# P00160_5_868_P.net
KiCad netlist of a schematic drawn in Altium Designer
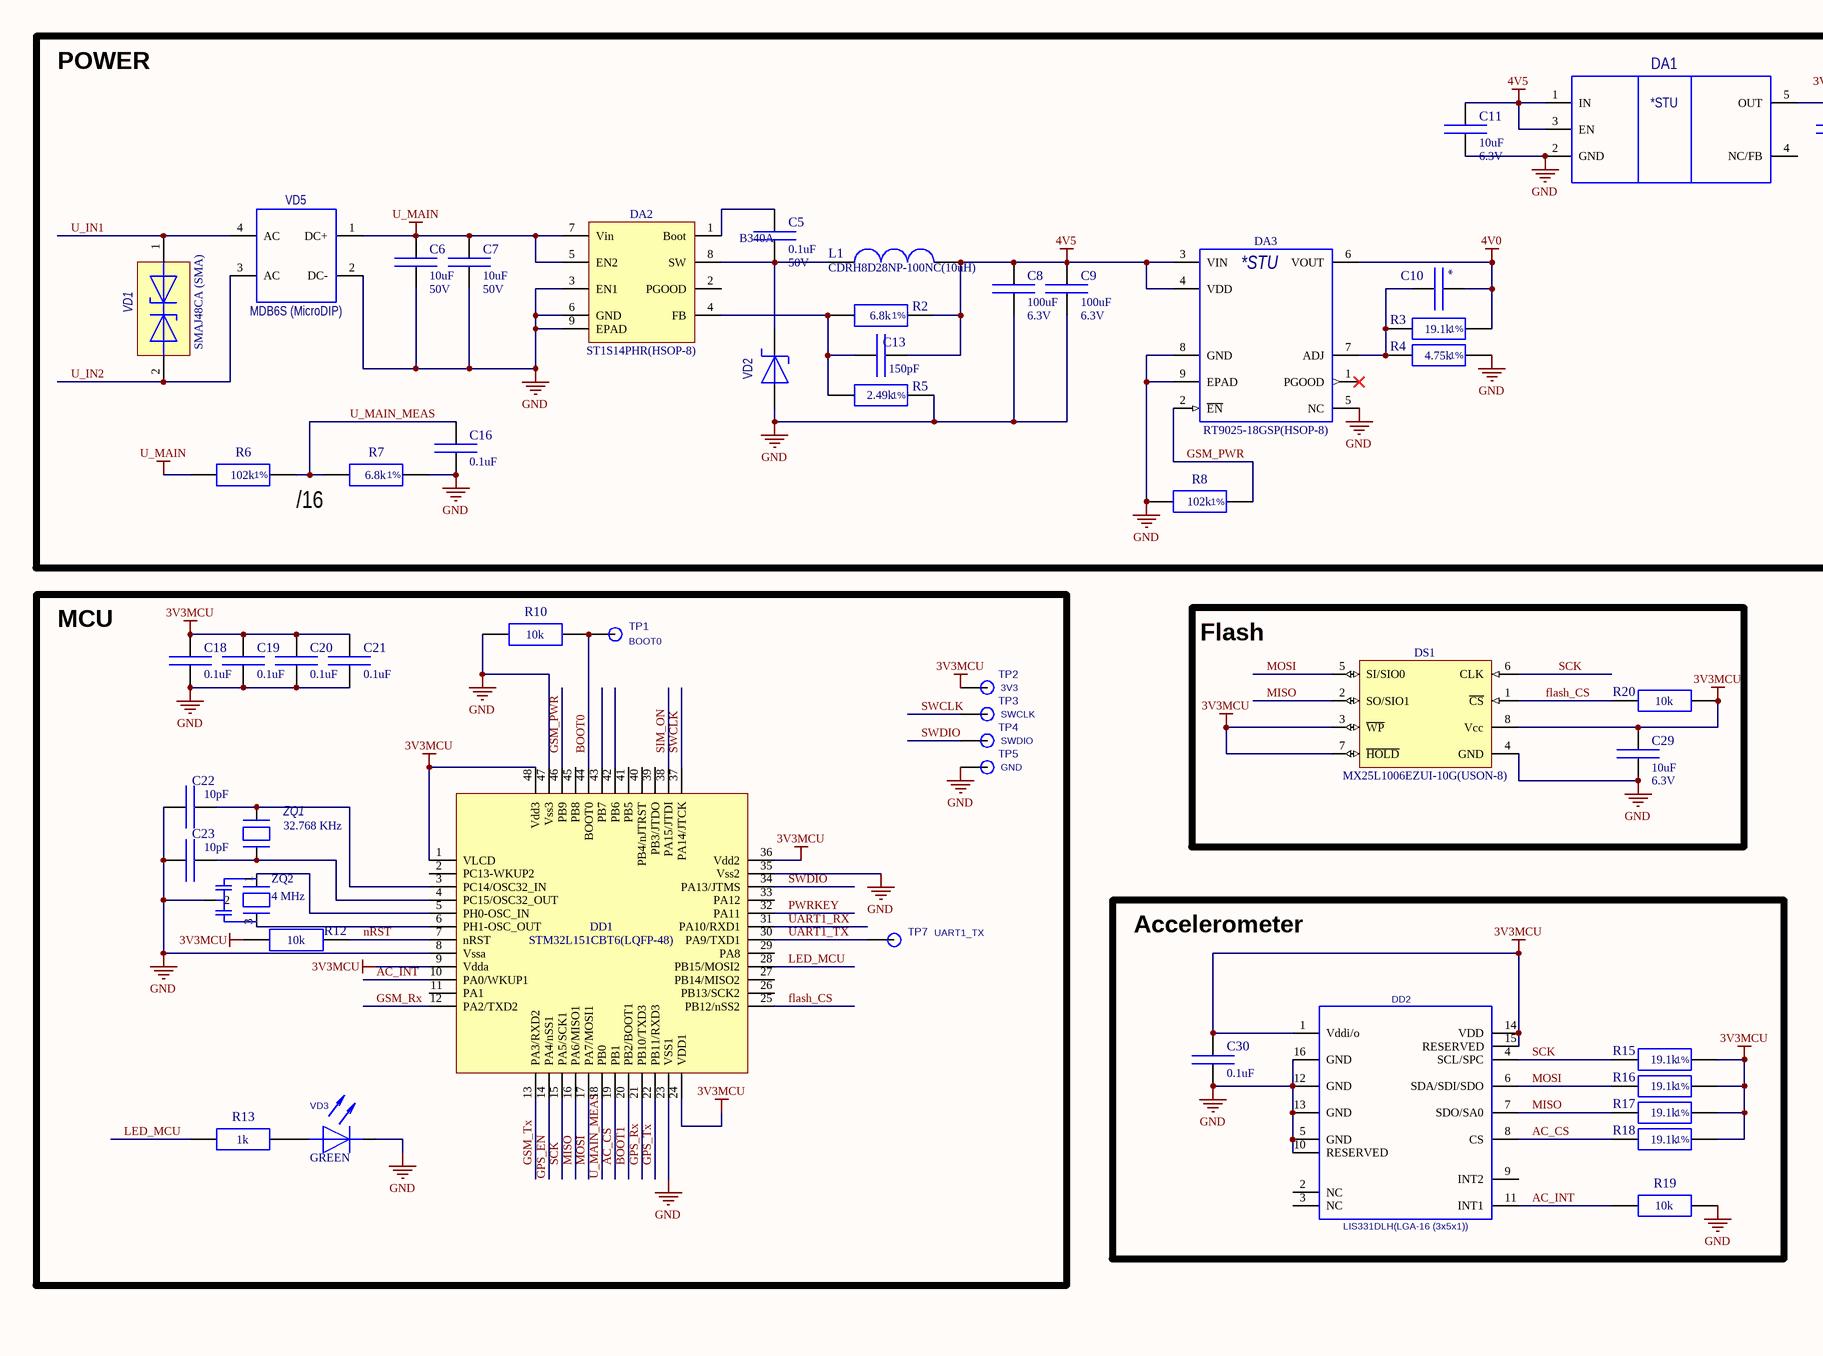
[diagram p0: P00160.5_868_P.SchDoc, left]
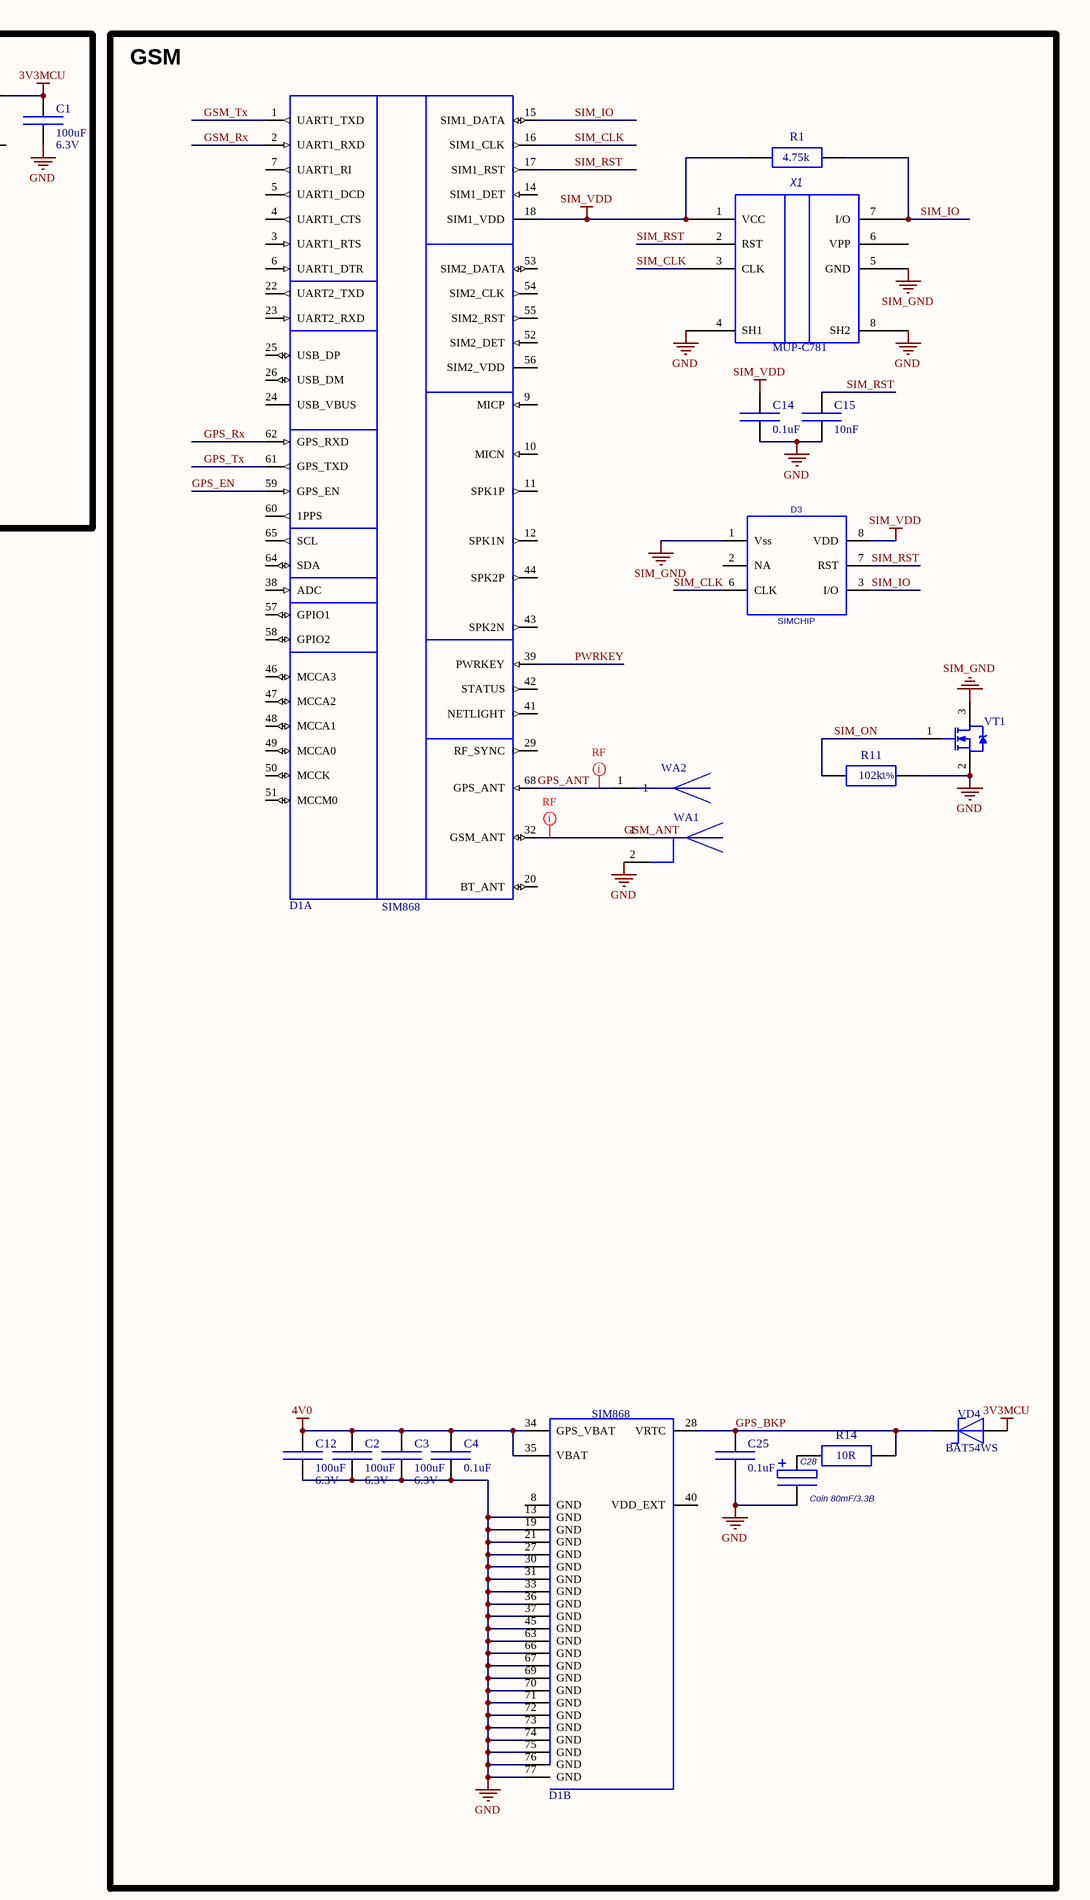
[diagram p1: P00160.5_868_P.SchDoc, right]

(export (version "E")
  (design (tool "Eeschema 10.0.6"))
  (components
    (comp (ref "C1")
      (value "100uF")
      (footprint "CAPC3216X135(1206)")
      (description "C1206")
      (fields (field (name "PARVOLTAGE") "6.3V") (field (name "Comment") "чип 1206 100uF/6.3V, "))
      (libsource (lib "pass_smd") (part "C1206"))
    )
    (comp (ref "C2")
      (value "100uF")
      (footprint "CAPC3216X135(1206)")
      (description "C1206")
      (fields (field (name "PARVOLTAGE") "6.3V") (field (name "Comment") "чип 1206 100uF/6.3V, "))
      (libsource (lib "pass_smd") (part "C1206"))
    )
    (comp (ref "C3")
      (value "100uF")
      (footprint "CAPC3216X135(1206)")
      (description "C1206")
      (fields (field (name "PARVOLTAGE") "6.3V") (field (name "Comment") "чип 1206 100uF/6.3V, "))
      (libsource (lib "pass_smd") (part "C1206"))
    )
    (comp (ref "C4")
      (value "0.1uF")
      (footprint "CAPC1005X50(0402)")
      (description "C0402")
      (fields (field (name "Comment") "чип 0402 0.1uF/10V, "))
      (libsource (lib "pass_smd") (part "C0402"))
    )
    (comp (ref "C5")
      (value "0.1uF")
      (footprint "CAPC1608X50(0603)")
      (description "C0603")
      (fields (field (name "PARVOLTAGE") "50V") (field (name "Comment") "чип 0603 0.1uF/50V, "))
      (libsource (lib "pass_smd") (part "C0603"))
    )
    (comp (ref "C6")
      (value "10uF")
      (footprint "CAPC3216X135(1206)")
      (description "C1206")
      (fields
        (field (name "CMPPARTNUM") "CL31A106KBHNNNE")
        (field (name "PARVOLTAGE") "50V")
        (field (name "Comment") "чип 1206 10uF/50V, ")
      )
      (libsource (lib "pass_smd") (part "C1206"))
    )
    (comp (ref "C7")
      (value "10uF")
      (footprint "CAPC3216X135(1206)")
      (description "C1206")
      (fields
        (field (name "CMPPARTNUM") "CL31A106KBHNNNE")
        (field (name "PARVOLTAGE") "50V")
        (field (name "Comment") "чип 1206 10uF/50V, ")
      )
      (libsource (lib "pass_smd") (part "C1206"))
    )
    (comp (ref "C8")
      (value "100uF")
      (footprint "CAPC3216X135(1206)")
      (description "C1206")
      (fields (field (name "PARVOLTAGE") "6.3V") (field (name "Comment") "чип 1206 100uF/6.3V, "))
      (libsource (lib "pass_smd") (part "C1206"))
    )
    (comp (ref "C9")
      (value "100uF")
      (footprint "CAPC3216X135(1206)")
      (description "C1206")
      (fields (field (name "PARVOLTAGE") "6.3V") (field (name "Comment") "чип 1206 100uF/6.3V, "))
      (libsource (lib "pass_smd") (part "C1206"))
    )
    (comp (ref "C10")
      (value "чип 0402 */,")
      (footprint "CAPC1005X50(0402)")
      (description "C0402")
      (fields (field (name "ALTIUM_VALUE") "*"))
      (libsource (lib "pass_smd") (part "C0402"))
    )
    (comp (ref "C11")
      (value "10uF")
      (footprint "CAPC1608X50(0603)")
      (description "C0603")
      (fields (field (name "PARVOLTAGE") "6.3V") (field (name "Comment") "чип 0603 10uF/6.3V, "))
      (libsource (lib "pass_smd") (part "C0603"))
    )
    (comp (ref "C12")
      (value "100uF")
      (footprint "CAPC3216X135(1206)")
      (description "C1206")
      (fields (field (name "PARVOLTAGE") "6.3V") (field (name "Comment") "чип 1206 100uF/6.3V, "))
      (libsource (lib "pass_smd") (part "C1206"))
    )
    (comp (ref "C13")
      (value "150pF")
      (footprint "CAPC1005X50(0402)")
      (description "C0402")
      (fields (field (name "Comment") "чип 0402 150pF/50V, "))
      (libsource (lib "pass_smd") (part "C0402"))
    )
    (comp (ref "C14")
      (value "0.1uF")
      (footprint "CAPC1005X50(0402)")
      (description "C0402")
      (fields (field (name "Comment") "чип 0402 0.1uF/10V, "))
      (libsource (lib "pass_smd") (part "C0402"))
    )
    (comp (ref "C15")
      (value "10nF")
      (footprint "CAPC1005X50(0402)")
      (description "C0402")
      (fields (field (name "Comment") "чип 0402 10nF/10V, "))
      (libsource (lib "pass_smd") (part "C0402"))
    )
    (comp (ref "C16")
      (value "0.1uF")
      (footprint "CAPC1005X50(0402)")
      (description "C0402")
      (fields (field (name "Comment") "чип 0402 0.1uF/10V, "))
      (libsource (lib "pass_smd") (part "C0402"))
    )
    (comp (ref "C18")
      (value "0.1uF")
      (footprint "CAPC1005X50(0402)")
      (description "C0402")
      (fields (field (name "Comment") "чип 0402 0.1uF/10V, "))
      (libsource (lib "pass_smd") (part "C0402"))
    )
    (comp (ref "C19")
      (value "0.1uF")
      (footprint "CAPC1005X50(0402)")
      (description "C0402")
      (fields (field (name "Comment") "чип 0402 0.1uF/10V, "))
      (libsource (lib "pass_smd") (part "C0402"))
    )
    (comp (ref "C20")
      (value "0.1uF")
      (footprint "CAPC1005X50(0402)")
      (description "C0402")
      (fields (field (name "Comment") "чип 0402 0.1uF/10V, "))
      (libsource (lib "pass_smd") (part "C0402"))
    )
    (comp (ref "C21")
      (value "0.1uF")
      (footprint "CAPC1005X50(0402)")
      (description "C0402")
      (fields (field (name "Comment") "чип 0402 0.1uF/10V, "))
      (libsource (lib "pass_smd") (part "C0402"))
    )
    (comp (ref "C22")
      (value "10pF")
      (footprint "CAPC1005X50(0402)")
      (description "C0402")
      (fields (field (name "Comment") "чип 0402 10pF/10V, "))
      (libsource (lib "pass_smd") (part "C0402"))
    )
    (comp (ref "C23")
      (value "10pF")
      (footprint "CAPC1005X50(0402)")
      (description "C0402")
      (fields (field (name "Comment") "чип 0402 10pF/10V, "))
      (libsource (lib "pass_smd") (part "C0402"))
    )
    (comp (ref "C25")
      (value "0.1uF")
      (footprint "CAPC1005X50(0402)")
      (description "C0402")
      (fields (field (name "Comment") "чип 0402 0.1uF/10V, "))
      (libsource (lib "pass_smd") (part "C0402"))
    )
    (comp (ref "C28")
      (value "Coin 80mF/3.3В")
      (footprint "XH414HG-IV01E")
      (description "ELECTRIC DOUBLE LAYER CAPACITORS")
      (fields (field (name "CMPPARTNUM") "XH414HG-IV01E"))
      (libsource (lib "MyLib") (part "XH414HG-IV01E"))
    )
    (comp (ref "C29")
      (value "10uF")
      (footprint "CAPC1608X50(0603)")
      (description "C0603")
      (fields (field (name "PARVOLTAGE") "6.3V") (field (name "Comment") "чип 0603 10uF/6.3V, "))
      (libsource (lib "pass_smd") (part "C0603"))
    )
    (comp (ref "C30")
      (value "0.1uF")
      (footprint "CAPC1005X50(0402)")
      (description "C0402")
      (fields (field (name "Comment") "чип 0402 0.1uF/10V, "))
      (libsource (lib "pass_smd") (part "C0402"))
    )
    (comp (ref "D1") (value "SIM868") (footprint "SIM868") (libsource (lib "") (part "SIM868_1")))
    (comp (ref "D3")
      (value "SIMCHIP")
      (footprint "VQFN127P600-8N")
      (fields (field (name "CMPPARTNUM") "MFF2 SIM"))
      (libsource (lib "Misc") (part "SIMCHIP"))
    )
    (comp (ref "DA1")
      (value "TPS76333DBV(SOT23-5)")
      (footprint "SOT95P285X130-5N(SOT23-5)")
      (description "TPS76333DBV")
      (libsource (lib "TI") (part "TPS76333DBV"))
    )
    (comp (ref "DA2")
      (value "ST1S14PHR(HSOP-8)")
      (footprint "HSOP127P-8N")
      (fields (field (name "CMPPARTNUM") "ST1S14PHR"))
      (libsource (lib "ST") (part "ST1S14"))
    )
    (comp (ref "DA3")
      (value "RT9025-18GSP(HSOP-8)")
      (footprint "HSOP127P-8N")
      (description "2A, Ultra Low Dropout LDO")
      (fields (field (name "CMPPARTNUM") "RT9025-18GSP"))
      (libsource (lib "Richtek") (part "RT9025"))
    )
    (comp (ref "DD1")
      (value "STM32L151CBT6(LQFP-48)")
      (footprint "TSQFP50P900X900X160-48N")
      (description "STM32L151CxU6")
      (fields (field (name "CMPPARTNUM") "STM32L151CBT6"))
      (libsource (lib "ST") (part "STM32L151CxU6"))
    )
    (comp (ref "DD2")
      (value "LIS331DLH(LGA-16 (3x5x1))")
      (footprint "LGA16S50P3X5_300X300X100")
      (description "MEMS digital output motion sensor  ultra low-power high performance 3-axes “nano” accelerometer")
      (fields (field (name "CMPPARTNUM") "LIS331DLH"))
      (libsource (lib "ST") (part "LIS331DLH"))
    )
    (comp (ref "DS1")
      (value "MX25L1006EZUI-10G(USON-8)")
      (footprint "SON50P300X60_HS-9N")
      (description "1M-BIT [x 1/x 2] CMOS SERIAL FLASH")
      (fields (field (name "CMPPARTNUM") "MX25L1006EZUI-10G"))
      (libsource (lib "ROMs") (part "MX25L1006E"))
    )
    (comp (ref "L1")
      (value "CDRH8D28NP-100NC(10uH)")
      (footprint "CDRH8D28NP")
      (description "CDRH8D28NP")
      (fields (field (name "CMPPARTNUM") "CDRH8D28NP-100NC"))
      (libsource (lib "pass_smd") (part "CDRH8D28NP"))
    )
    (comp (ref "R1")
      (value "4.75k")
      (footprint "RESC1005X35(0402)")
      (description "R0402")
      (fields (field (name "TOLERANCE") "1%") (field (name "Comment") "чип 0402 4.75k 1%"))
      (libsource (lib "pass_smd") (part "R0402"))
    )
    (comp (ref "R2")
      (value "6.8k")
      (footprint "RESC1005X35(0402)")
      (description "R0402")
      (fields (field (name "TOLERANCE") "1%") (field (name "Comment") "чип 0402 6.8k 1%"))
      (libsource (lib "pass_smd") (part "R0402"))
    )
    (comp (ref "R3")
      (value "19.1k")
      (footprint "RESC1005X35(0402)")
      (description "R0402")
      (fields (field (name "TOLERANCE") "1%") (field (name "Comment") "чип 0402 19.1k 1%"))
      (libsource (lib "pass_smd") (part "R0402"))
    )
    (comp (ref "R4")
      (value "4.75k")
      (footprint "RESC1005X35(0402)")
      (description "R0402")
      (fields (field (name "TOLERANCE") "1%") (field (name "Comment") "чип 0402 4.75k 1%"))
      (libsource (lib "pass_smd") (part "R0402"))
    )
    (comp (ref "R5")
      (value "2.49k")
      (footprint "RESC1005X35(0402)")
      (description "R0402")
      (fields (field (name "TOLERANCE") "1%") (field (name "Comment") "чип 0402 2.49k 1%"))
      (libsource (lib "pass_smd") (part "R0402"))
    )
    (comp (ref "R6")
      (value "102k")
      (footprint "RESC1005X35(0402)")
      (description "R0402")
      (fields (field (name "TOLERANCE") "1%") (field (name "Comment") "чип 0402 102k 1%"))
      (libsource (lib "pass_smd") (part "R0402"))
    )
    (comp (ref "R7")
      (value "6.8k")
      (footprint "RESC1005X35(0402)")
      (description "R0402")
      (fields (field (name "TOLERANCE") "1%") (field (name "Comment") "чип 0402 6.8k 1%"))
      (libsource (lib "pass_smd") (part "R0402"))
    )
    (comp (ref "R8")
      (value "102k")
      (footprint "RESC1005X35(0402)")
      (description "R0402")
      (fields (field (name "TOLERANCE") "1%") (field (name "Comment") "чип 0402 102k 1%"))
      (libsource (lib "pass_smd") (part "R0402"))
    )
    (comp (ref "R10")
      (value "10k")
      (footprint "RESC1005X35(0402)")
      (description "R0402")
      (fields (field (name "TOLERANCE") "5%") (field (name "Comment") "чип 0402 10k 5%"))
      (libsource (lib "pass_smd") (part "R0402"))
    )
    (comp (ref "R11")
      (value "102k")
      (footprint "RESC1005X35(0402)")
      (description "R0402")
      (fields (field (name "TOLERANCE") "1%") (field (name "Comment") "чип 0402 102k 1%"))
      (libsource (lib "pass_smd") (part "R0402"))
    )
    (comp (ref "R12")
      (value "10k")
      (footprint "RESC1005X35(0402)")
      (description "R0402")
      (fields (field (name "TOLERANCE") "5%") (field (name "Comment") "чип 0402 10k 5%"))
      (libsource (lib "pass_smd") (part "R0402"))
    )
    (comp (ref "R13")
      (value "1k")
      (footprint "RESC1005X35(0402)")
      (description "R0402")
      (fields (field (name "TOLERANCE") "5%") (field (name "Comment") "чип 0402 1k 5%"))
      (libsource (lib "pass_smd") (part "R0402"))
    )
    (comp (ref "R14")
      (value "10R")
      (footprint "RESC1005X35(0402)")
      (description "R0402")
      (fields (field (name "TOLERANCE") "5%") (field (name "Comment") "чип 0402 10R 5%"))
      (libsource (lib "pass_smd") (part "R0402"))
    )
    (comp (ref "R15")
      (value "19.1k")
      (footprint "RESC1005X35(0402)")
      (description "R0402")
      (fields (field (name "TOLERANCE") "1%") (field (name "Comment") "чип 0402 19.1k 1%"))
      (libsource (lib "pass_smd") (part "R0402"))
    )
    (comp (ref "R16")
      (value "19.1k")
      (footprint "RESC1005X35(0402)")
      (description "R0402")
      (fields (field (name "TOLERANCE") "1%") (field (name "Comment") "чип 0402 19.1k 1%"))
      (libsource (lib "pass_smd") (part "R0402"))
    )
    (comp (ref "R17")
      (value "19.1k")
      (footprint "RESC1005X35(0402)")
      (description "R0402")
      (fields (field (name "TOLERANCE") "1%") (field (name "Comment") "чип 0402 19.1k 1%"))
      (libsource (lib "pass_smd") (part "R0402"))
    )
    (comp (ref "R18")
      (value "19.1k")
      (footprint "RESC1005X35(0402)")
      (description "R0402")
      (fields (field (name "TOLERANCE") "1%") (field (name "Comment") "чип 0402 19.1k 1%"))
      (libsource (lib "pass_smd") (part "R0402"))
    )
    (comp (ref "R19")
      (value "10k")
      (footprint "RESC1005X35(0402)")
      (description "R0402")
      (fields (field (name "TOLERANCE") "5%") (field (name "Comment") "чип 0402 10k 5%"))
      (libsource (lib "pass_smd") (part "R0402"))
    )
    (comp (ref "R20")
      (value "10k")
      (footprint "RESC1005X35(0402)")
      (description "R0402")
      (fields (field (name "TOLERANCE") "5%") (field (name "Comment") "чип 0402 10k 5%"))
      (libsource (lib "pass_smd") (part "R0402"))
    )
    (comp (ref "TP1")
      (value "BOOT0")
      (footprint "TEST_POINT")
      (description "TEST_POINT")
      (libsource (lib "connectors") (part "TEST_POINT"))
    )
    (comp (ref "TP2")
      (value "3V3")
      (footprint "TEST_POINT")
      (description "TEST_POINT")
      (libsource (lib "connectors") (part "TEST_POINT"))
    )
    (comp (ref "TP3")
      (value "SWCLK")
      (footprint "TEST_POINT")
      (description "TEST_POINT")
      (libsource (lib "connectors") (part "TEST_POINT"))
    )
    (comp (ref "TP4")
      (value "SWDIO")
      (footprint "TEST_POINT")
      (description "TEST_POINT")
      (libsource (lib "connectors") (part "TEST_POINT"))
    )
    (comp (ref "TP5")
      (value "GND")
      (footprint "TEST_POINT")
      (description "TEST_POINT")
      (libsource (lib "connectors") (part "TEST_POINT"))
    )
    (comp (ref "TP7")
      (value "UART1_TX")
      (footprint "TEST_POINT")
      (description "TEST_POINT")
      (libsource (lib "connectors") (part "TEST_POINT"))
    )
    (comp (ref "VD1")
      (value "SMAJ48CA (SMA)")
      (footprint "DIOM5226X267N (SMA) B")
      (description "Zener (TVS) Diode in SMA package Bidirectional")
      (fields (field (name "CMPPARTNUM") "SMAJ48CA"))
      (libsource (lib "diodes") (part "SMA Zener (Bidir)"))
    )
    (comp (ref "VD2")
      (value "B340A (SMA)")
      (footprint "DIOM5226X267N (SMA)")
      (description "Schottky diode in SMA Case")
      (fields (field (name "CMPPARTNUM") "B340A"))
      (libsource (lib "diodes") (part "SMA SCHOTTKY"))
    )
    (comp (ref "VD3")
      (value "APHHS1005SURCK (чип 0402)")
      (footprint "LED1005X50N(0402)_GREEN")
      (description "LED 0402")
      (fields (field (name "CMPPARTNUM") "APHHS1005SURCK") (field (name "PARCOLOR") "GREEN"))
      (libsource (lib "diodes") (part "LED 0402"))
    )
    (comp (ref "VD4")
      (value "BAT54WS (SOD323)")
      (footprint "SOD2514X110N(SOD323)")
      (description "BAT54WS")
      (fields (field (name "CMPPARTNUM") "BAT54WS"))
      (libsource (lib "diodes") (part "SOD323 SCHOTTKY"))
    )
    (comp (ref "VD5")
      (value "MDB6S (MicroDIP)")
      (footprint "Micro-DIP")
      (description "B1S-B10S 0.5 surface mount glass passivated bridge rectifier")
      (fields (field (name "CMPPARTNUM") "MDB6S"))
      (libsource (lib "diodes") (part "MDB6S"))
    )
    (comp (ref "VT1")
      (value "IRLML0030TRPBF (SOT-23)")
      (footprint "SOT95P230-3N (SOT-23) num")
      (description "HEXFET Power MOSFET")
      (fields (field (name "CMPPARTNUM") "IRLML0030TRPBF"))
      (libsource (lib "transistors") (part "IRLML0030"))
    )
    (comp (ref "WA1")
      (value "~")
      (footprint "PCB_ANT")
      (description "CLIP_ANT")
      (libsource (lib "MyLib") (part "ANT_PCB_CLIP"))
    )
    (comp (ref "WA2")
      (value "UDA182-180-1575-C-GPS-GLONASS-PCB")
      (footprint "UDA184")
      (description "A25, UDA25, A18")
      (libsource (lib "Misc") (part "GPS antenna Pass"))
    )
    (comp (ref "X1")
      (value "MUP Connectors MUP-C781")
      (footprint "MUP-C781")
      (description "Sim Holder MUP-C781")
      (fields (field (name "CMPPARTNUM") "MUP-C781"))
      (libsource (lib "connectors") (part "SIM MUP-C781"))
    )
    (comp (ref "ZQ1")
      (value "32.768 KHz")
      (footprint "XTAL320X150X90-2N(DST)")
      (description "DST310S")
      (fields (field (name "Comment") "DST310S(32.768 KHz)"))
      (libsource (lib "xtal") (part "XTAL, SMD, 3.2mm x 1.5mm, 2 pads"))
    )
    (comp (ref "ZQ2")
      (value "4 MHz")
      (footprint "XTAL450X200X120 (CSTCR)")
      (description "CSTCR_G15C Ceramic Resonators")
      (fields (field (name "CMPPARTNUM") "CSTCR4M00G15C99-R0") (field (name "TOLERANCE") "±0.5%"))
      (libsource (lib "xtal") (part "XTAL, SMD, 4.5mm x 2mm, 3 pads"))
    )
  )
  (nets
    (net (code "1") (name "/AC_CS") (class "Default")
      (node (ref "DD1") (pin "19") (pinfunction "PB1_19") (pintype "passive"))
      (node (ref "DD2") (pin "8") (pinfunction "CS_8") (pintype "passive"))
      (node (ref "R18") (pin "1") (pinfunction "1_1") (pintype "passive"))
    )
    (net (code "2") (name "/AC_INT") (class "Default")
      (node (ref "DD1") (pin "10") (pinfunction "PA0/WKUP1_10") (pintype "passive"))
      (node (ref "DD2") (pin "11") (pinfunction "INT1_11") (pintype "passive"))
      (node (ref "R19") (pin "1") (pinfunction "1_1") (pintype "passive"))
    )
    (net (code "3") (name "/BOOT0") (class "Default")
      (node (ref "DD1") (pin "44") (pinfunction "BOOT0_44") (pintype "passive"))
      (node (ref "R10") (pin "2") (pinfunction "2_2") (pintype "passive"))
      (node (ref "TP1") (pin "1") (pintype "passive"))
    )
    (net (code "4") (name "/BOOT1") (class "Default")
      (node (ref "DD1") (pin "20") (pinfunction "PB2/BOOT1_20") (pintype "passive"))
    )
    (net (code "5") (name "/GPS_ANT") (class "Default")
      (node (ref "D1") (pin "68") (pinfunction "GPS_ANT_68") (pintype "input"))
      (node (ref "WA2") (pin "1") (pinfunction "1_1") (pintype "passive"))
    )
    (net (code "6") (name "/GPS_BKP") (class "Default")
      (node (ref "C25") (pin "2") (pinfunction "P2_2") (pintype "passive"))
      (node (ref "D1") (pin "28") (pinfunction "VRTC_28") (pintype "power_in"))
      (node (ref "R14") (pin "2") (pinfunction "2_2") (pintype "passive"))
      (node (ref "VD4") (pin "C") (pinfunction "C_C") (pintype "passive"))
    )
    (net (code "7") (name "/GPS_EN") (class "Default")
      (node (ref "D1") (pin "59") (pinfunction "GPS_EN_59") (pintype "input"))
      (node (ref "DD1") (pin "14") (pinfunction "PA4/nSS1_14") (pintype "passive"))
    )
    (net (code "8") (name "/GPS_Rx") (class "Default")
      (node (ref "D1") (pin "62") (pinfunction "GPS_RXD_62") (pintype "input"))
      (node (ref "DD1") (pin "21") (pinfunction "PB10/TXD3_21") (pintype "passive"))
    )
    (net (code "9") (name "/GPS_Tx") (class "Default")
      (node (ref "D1") (pin "61") (pinfunction "GPS_TXD_61") (pintype "output"))
      (node (ref "DD1") (pin "22") (pinfunction "PB11/RXD3_22") (pintype "passive"))
    )
    (net (code "10") (name "/GSM_ANT") (class "Default")
      (node (ref "D1") (pin "32") (pinfunction "GSM_ANT_32") (pintype "bidirectional"))
      (node (ref "WA1") (pin "1") (pinfunction "1_1") (pintype "passive"))
    )
    (net (code "11") (name "/GSM_PWR") (class "Default")
      (node (ref "DA3") (pin "2") (pinfunction "~{EN}_2") (pintype "input"))
      (node (ref "DD1") (pin "46") (pinfunction "PB9_46") (pintype "passive"))
      (node (ref "R8") (pin "2") (pinfunction "2_2") (pintype "passive"))
    )
    (net (code "12") (name "/GSM_Rx") (class "Default")
      (node (ref "D1") (pin "2") (pinfunction "UART1_RXD_2") (pintype "input"))
      (node (ref "DD1") (pin "12") (pinfunction "PA2/TXD2_12") (pintype "passive"))
    )
    (net (code "13") (name "/GSM_Tx") (class "Default")
      (node (ref "D1") (pin "1") (pinfunction "UART1_TXD_1") (pintype "output"))
      (node (ref "DD1") (pin "13") (pinfunction "PA3/RXD2_13") (pintype "passive"))
    )
    (net (code "14") (name "/LED_MCU") (class "Default")
      (node (ref "DD1") (pin "28") (pinfunction "PB15/MOSI2_28") (pintype "passive"))
      (node (ref "R13") (pin "1") (pinfunction "1_1") (pintype "passive"))
    )
    (net (code "15") (name "/MISO") (class "Default")
      (node (ref "DD1") (pin "16") (pinfunction "PA6/MISO1_16") (pintype "passive"))
      (node (ref "DD2") (pin "7") (pinfunction "SDO/SA0_7") (pintype "passive"))
      (node (ref "DS1") (pin "2") (pinfunction "SO/SIO1_2") (pintype "bidirectional"))
      (node (ref "R17") (pin "1") (pinfunction "1_1") (pintype "passive"))
    )
    (net (code "16") (name "/MOSI") (class "Default")
      (node (ref "DD1") (pin "17") (pinfunction "PA7/MOSI1_17") (pintype "passive"))
      (node (ref "DD2") (pin "6") (pinfunction "SDA/SDI/SDO_6") (pintype "passive"))
      (node (ref "DS1") (pin "5") (pinfunction "SI/SIO0_5") (pintype "bidirectional"))
      (node (ref "R16") (pin "1") (pinfunction "1_1") (pintype "passive"))
    )
    (net (code "17") (name "/PWRKEY") (class "Default")
      (node (ref "D1") (pin "39") (pinfunction "PWRKEY_39") (pintype "input"))
      (node (ref "DD1") (pin "32") (pinfunction "PA11_32") (pintype "passive"))
    )
    (net (code "18") (name "/SCK") (class "Default")
      (node (ref "DD1") (pin "15") (pinfunction "PA5/SCK1_15") (pintype "passive"))
      (node (ref "DD2") (pin "4") (pinfunction "SCL/SPC_4") (pintype "passive"))
      (node (ref "DS1") (pin "6") (pinfunction "CLK_6") (pintype "input"))
      (node (ref "R15") (pin "1") (pinfunction "1_1") (pintype "passive"))
    )
    (net (code "19") (name "/SIM_CLK") (class "Default")
      (node (ref "D1") (pin "16") (pinfunction "SIM1_CLK_16") (pintype "output"))
      (node (ref "D3") (pin "6") (pinfunction "CLK_6") (pintype "passive"))
      (node (ref "X1") (pin "3") (pinfunction "CLK_3") (pintype "passive"))
    )
    (net (code "20") (name "/SIM_IO") (class "Default")
      (node (ref "D1") (pin "15") (pinfunction "SIM1_DATA_15") (pintype "bidirectional"))
      (node (ref "D3") (pin "3") (pinfunction "I/O_3") (pintype "passive"))
      (node (ref "R1") (pin "2") (pinfunction "2_2") (pintype "passive"))
      (node (ref "X1") (pin "7") (pinfunction "I/O_7") (pintype "passive"))
    )
    (net (code "21") (name "/SIM_ON") (class "Default")
      (node (ref "DD1") (pin "38") (pinfunction "PA15/JTDI_38") (pintype "passive"))
      (node (ref "R11") (pin "1") (pinfunction "1_1") (pintype "passive"))
      (node (ref "VT1") (pin "1") (pinfunction "G_1") (pintype "passive"))
    )
    (net (code "22") (name "/SIM_RST") (class "Default")
      (node (ref "C15") (pin "2") (pinfunction "P2_2") (pintype "passive"))
      (node (ref "D1") (pin "17") (pinfunction "SIM1_RST_17") (pintype "output"))
      (node (ref "D3") (pin "7") (pinfunction "RST_7") (pintype "passive"))
      (node (ref "X1") (pin "2") (pinfunction "RST_2") (pintype "passive"))
    )
    (net (code "23") (name "/SWCLK") (class "Default")
      (node (ref "DD1") (pin "37") (pinfunction "PA14/JTCK_37") (pintype "passive"))
      (node (ref "TP3") (pin "1") (pintype "passive"))
    )
    (net (code "24") (name "/SWDIO") (class "Default")
      (node (ref "DD1") (pin "34") (pinfunction "PA13/JTMS_34") (pintype "passive"))
      (node (ref "TP4") (pin "1") (pintype "passive"))
    )
    (net (code "25") (name "/UART1_RX") (class "Default")
      (node (ref "DD1") (pin "31") (pinfunction "PA10/RXD1_31") (pintype "passive"))
    )
    (net (code "26") (name "/UART1_TX") (class "Default")
      (node (ref "DD1") (pin "30") (pinfunction "PA9/TXD1_30") (pintype "passive"))
      (node (ref "TP7") (pin "1") (pintype "passive"))
    )
    (net (code "27") (name "/U_IN1") (class "Default")
      (node (ref "VD1") (pin "1") (pinfunction "1_1") (pintype "passive"))
      (node (ref "VD5") (pin "4") (pinfunction "AC_4") (pintype "passive"))
    )
    (net (code "28") (name "/U_IN2") (class "Default")
      (node (ref "VD1") (pin "2") (pinfunction "2_2") (pintype "passive"))
      (node (ref "VD5") (pin "3") (pinfunction "AC_3") (pintype "passive"))
    )
    (net (code "29") (name "/U_MAIN_MEAS") (class "Default")
      (node (ref "C16") (pin "2") (pinfunction "P2_2") (pintype "passive"))
      (node (ref "DD1") (pin "18") (pinfunction "PB0_18") (pintype "passive"))
      (node (ref "R6") (pin "2") (pinfunction "2_2") (pintype "passive"))
      (node (ref "R7") (pin "1") (pinfunction "1_1") (pintype "passive"))
    )
    (net (code "30") (name "/flash_CS") (class "Default")
      (node (ref "DD1") (pin "25") (pinfunction "PB12/nSS2_25") (pintype "passive"))
      (node (ref "DS1") (pin "1") (pinfunction "CS_1") (pintype "input"))
      (node (ref "R20") (pin "1") (pinfunction "1_1") (pintype "passive"))
    )
    (net (code "31") (name "/nRST") (class "Default")
      (node (ref "DD1") (pin "7") (pinfunction "nRST_7") (pintype "passive"))
      (node (ref "R12") (pin "2") (pinfunction "2_2") (pintype "passive"))
    )
    (net (code "32") (name "3V3MCU") (class "Default")
      (node (ref "C1") (pin "1") (pinfunction "1_1") (pintype "passive"))
      (node (ref "C18") (pin "2") (pinfunction "P2_2") (pintype "passive"))
      (node (ref "C19") (pin "2") (pinfunction "P2_2") (pintype "passive"))
      (node (ref "C20") (pin "2") (pinfunction "P2_2") (pintype "passive"))
      (node (ref "C21") (pin "2") (pinfunction "P2_2") (pintype "passive"))
      (node (ref "C29") (pin "2") (pinfunction "2_2") (pintype "passive"))
      (node (ref "C30") (pin "2") (pinfunction "P2_2") (pintype "passive"))
      (node (ref "DA1") (pin "5") (pinfunction "OUT_5") (pintype "passive"))
      (node (ref "DD1") (pin "1") (pinfunction "VLCD_1") (pintype "passive"))
      (node (ref "DD1") (pin "24") (pinfunction "VDD1_24") (pintype "passive"))
      (node (ref "DD1") (pin "36") (pinfunction "Vdd2_36") (pintype "passive"))
      (node (ref "DD1") (pin "48") (pinfunction "Vdd3_48") (pintype "passive"))
      (node (ref "DD1") (pin "9") (pinfunction "Vdda_9") (pintype "passive"))
      (node (ref "DD2") (pin "1") (pinfunction "Vddi/o_1") (pintype "passive"))
      (node (ref "DD2") (pin "14") (pinfunction "VDD_14") (pintype "passive"))
      (node (ref "DD2") (pin "15") (pinfunction "RESERVED_15") (pintype "passive"))
      (node (ref "DS1") (pin "3") (pinfunction "~{WP}_3") (pintype "bidirectional"))
      (node (ref "DS1") (pin "7") (pinfunction "~{HOLD}_7") (pintype "bidirectional"))
      (node (ref "DS1") (pin "8") (pinfunction "Vcc_8") (pintype "passive"))
      (node (ref "R12") (pin "1") (pinfunction "1_1") (pintype "passive"))
      (node (ref "R15") (pin "2") (pinfunction "2_2") (pintype "passive"))
      (node (ref "R16") (pin "2") (pinfunction "2_2") (pintype "passive"))
      (node (ref "R17") (pin "2") (pinfunction "2_2") (pintype "passive"))
      (node (ref "R18") (pin "2") (pinfunction "2_2") (pintype "passive"))
      (node (ref "R20") (pin "2") (pinfunction "2_2") (pintype "passive"))
      (node (ref "TP2") (pin "1") (pintype "passive"))
      (node (ref "VD4") (pin "A") (pinfunction "A_A") (pintype "passive"))
    )
    (net (code "33") (name "4V0") (class "Default")
      (node (ref "C10") (pin "1") (pinfunction "P1_1") (pintype "passive"))
      (node (ref "C12") (pin "1") (pinfunction "1_1") (pintype "passive"))
      (node (ref "C2") (pin "1") (pinfunction "1_1") (pintype "passive"))
      (node (ref "C3") (pin "1") (pinfunction "1_1") (pintype "passive"))
      (node (ref "C4") (pin "2") (pinfunction "P2_2") (pintype "passive"))
      (node (ref "D1") (pin "34") (pinfunction "GPS_VBAT_34") (pintype "power_in"))
      (node (ref "D1") (pin "35") (pinfunction "VBAT_35") (pintype "power_in"))
      (node (ref "DA3") (pin "6") (pinfunction "VOUT_6") (pintype "power_in"))
      (node (ref "R3") (pin "2") (pinfunction "2_2") (pintype "passive"))
    )
    (net (code "34") (name "4V5") (class "Default")
      (node (ref "C11") (pin "2") (pinfunction "2_2") (pintype "passive"))
      (node (ref "C13") (pin "1") (pinfunction "P1_1") (pintype "passive"))
      (node (ref "C8") (pin "1") (pinfunction "1_1") (pintype "passive"))
      (node (ref "C9") (pin "1") (pinfunction "1_1") (pintype "passive"))
      (node (ref "DA1") (pin "1") (pinfunction "IN_1") (pintype "passive"))
      (node (ref "DA1") (pin "3") (pinfunction "EN_3") (pintype "passive"))
      (node (ref "DA3") (pin "3") (pinfunction "VIN_3") (pintype "power_in"))
      (node (ref "DA3") (pin "4") (pinfunction "VDD_4") (pintype "power_in"))
      (node (ref "L1") (pin "2") (pinfunction "2_2") (pintype "passive"))
      (node (ref "R2") (pin "2") (pinfunction "2_2") (pintype "passive"))
    )
    (net (code "35") (name "GND") (class "Default")
      (node (ref "C1") (pin "2") (pinfunction "2_2") (pintype "passive"))
      (node (ref "C11") (pin "1") (pinfunction "1_1") (pintype "passive"))
      (node (ref "C12") (pin "2") (pinfunction "2_2") (pintype "passive"))
      (node (ref "C14") (pin "1") (pinfunction "P1_1") (pintype "passive"))
      (node (ref "C15") (pin "1") (pinfunction "P1_1") (pintype "passive"))
      (node (ref "C16") (pin "1") (pinfunction "P1_1") (pintype "passive"))
      (node (ref "C18") (pin "1") (pinfunction "P1_1") (pintype "passive"))
      (node (ref "C19") (pin "1") (pinfunction "P1_1") (pintype "passive"))
      (node (ref "C2") (pin "2") (pinfunction "2_2") (pintype "passive"))
      (node (ref "C20") (pin "1") (pinfunction "P1_1") (pintype "passive"))
      (node (ref "C21") (pin "1") (pinfunction "P1_1") (pintype "passive"))
      (node (ref "C22") (pin "2") (pinfunction "P2_2") (pintype "passive"))
      (node (ref "C23") (pin "2") (pinfunction "P2_2") (pintype "passive"))
      (node (ref "C25") (pin "1") (pinfunction "P1_1") (pintype "passive"))
      (node (ref "C28") (pin "2") (pinfunction "2_2") (pintype "passive"))
      (node (ref "C29") (pin "1") (pinfunction "1_1") (pintype "passive"))
      (node (ref "C3") (pin "2") (pinfunction "2_2") (pintype "passive"))
      (node (ref "C30") (pin "1") (pinfunction "P1_1") (pintype "passive"))
      (node (ref "C4") (pin "1") (pinfunction "P1_1") (pintype "passive"))
      (node (ref "C6") (pin "2") (pinfunction "2_2") (pintype "passive"))
      (node (ref "C7") (pin "2") (pinfunction "2_2") (pintype "passive"))
      (node (ref "C8") (pin "2") (pinfunction "2_2") (pintype "passive"))
      (node (ref "C9") (pin "2") (pinfunction "2_2") (pintype "passive"))
      (node (ref "D1") (pin "13") (pinfunction "GND_13") (pintype "power_in"))
      (node (ref "D1") (pin "19") (pinfunction "GND_19") (pintype "power_in"))
      (node (ref "D1") (pin "21") (pinfunction "GND_21") (pintype "power_in"))
      (node (ref "D1") (pin "27") (pinfunction "GND_27") (pintype "power_in"))
      (node (ref "D1") (pin "30") (pinfunction "GND_30") (pintype "power_in"))
      (node (ref "D1") (pin "31") (pinfunction "GND_31") (pintype "power_in"))
      (node (ref "D1") (pin "33") (pinfunction "GND_33") (pintype "power_in"))
      (node (ref "D1") (pin "36") (pinfunction "GND_36") (pintype "power_in"))
      (node (ref "D1") (pin "37") (pinfunction "GND_37") (pintype "power_in"))
      (node (ref "D1") (pin "45") (pinfunction "GND_45") (pintype "power_in"))
      (node (ref "D1") (pin "63") (pinfunction "GND_63") (pintype "power_in"))
      (node (ref "D1") (pin "66") (pinfunction "GND_66") (pintype "power_in"))
      (node (ref "D1") (pin "67") (pinfunction "GND_67") (pintype "power_in"))
      (node (ref "D1") (pin "69") (pinfunction "GND_69") (pintype "power_in"))
      (node (ref "D1") (pin "70") (pinfunction "GND_70") (pintype "power_in"))
      (node (ref "D1") (pin "71") (pinfunction "GND_71") (pintype "power_in"))
      (node (ref "D1") (pin "72") (pinfunction "GND_72") (pintype "power_in"))
      (node (ref "D1") (pin "73") (pinfunction "GND_73") (pintype "power_in"))
      (node (ref "D1") (pin "74") (pinfunction "GND_74") (pintype "power_in"))
      (node (ref "D1") (pin "75") (pinfunction "GND_75") (pintype "power_in"))
      (node (ref "D1") (pin "76") (pinfunction "GND_76") (pintype "power_in"))
      (node (ref "D1") (pin "77") (pinfunction "GND_77") (pintype "power_in"))
      (node (ref "DA1") (pin "2") (pinfunction "GND_2") (pintype "passive"))
      (node (ref "DA2") (pin "3") (pinfunction "EN1_3") (pintype "passive"))
      (node (ref "DA2") (pin "6") (pinfunction "GND_6") (pintype "passive"))
      (node (ref "DA2") (pin "9") (pinfunction "EPAD_9") (pintype "passive"))
      (node (ref "DA3") (pin "5") (pinfunction "NC_5") (pintype "passive"))
      (node (ref "DA3") (pin "8") (pinfunction "GND_8") (pintype "power_in"))
      (node (ref "DA3") (pin "9") (pinfunction "EPAD_9") (pintype "power_in"))
      (node (ref "DD1") (pin "23") (pinfunction "VSS1_23") (pintype "passive"))
      (node (ref "DD1") (pin "35") (pinfunction "Vss2_35") (pintype "passive"))
      (node (ref "DD1") (pin "47") (pinfunction "Vss3_47") (pintype "passive"))
      (node (ref "DD1") (pin "8") (pinfunction "Vssa_8") (pintype "passive"))
      (node (ref "DD2") (pin "10") (pinfunction "RESERVED_10") (pintype "passive"))
      (node (ref "DD2") (pin "12") (pinfunction "GND_12") (pintype "passive"))
      (node (ref "DD2") (pin "13") (pinfunction "GND_13") (pintype "passive"))
      (node (ref "DD2") (pin "16") (pinfunction "GND_16") (pintype "passive"))
      (node (ref "DD2") (pin "5") (pinfunction "GND_5") (pintype "passive"))
      (node (ref "DS1") (pin "4") (pinfunction "GND_4") (pintype "passive"))
      (node (ref "R10") (pin "1") (pinfunction "1_1") (pintype "passive"))
      (node (ref "R11") (pin "2") (pinfunction "2_2") (pintype "passive"))
      (node (ref "R19") (pin "2") (pinfunction "2_2") (pintype "passive"))
      (node (ref "R4") (pin "2") (pinfunction "2_2") (pintype "passive"))
      (node (ref "R5") (pin "2") (pinfunction "2_2") (pintype "passive"))
      (node (ref "R7") (pin "2") (pinfunction "2_2") (pintype "passive"))
      (node (ref "R8") (pin "1") (pinfunction "1_1") (pintype "passive"))
      (node (ref "TP5") (pin "1") (pintype "passive"))
      (node (ref "VD2") (pin "A") (pinfunction "1_A") (pintype "passive"))
      (node (ref "VD3") (pin "C") (pinfunction "cathode_C") (pintype "passive"))
      (node (ref "VD5") (pin "2") (pinfunction "DC-_2") (pintype "passive"))
      (node (ref "VT1") (pin "2") (pinfunction "S_2") (pintype "passive"))
      (node (ref "WA1") (pin "2") (pinfunction "2_2") (pintype "power_in"))
      (node (ref "X1") (pin "4") (pinfunction "SH1_4") (pintype "passive"))
      (node (ref "X1") (pin "8") (pinfunction "SH2_8") (pintype "passive"))
      (node (ref "ZQ2") (pin "2") (pinfunction "2_2") (pintype "passive"))
    )
    (net (code "36") (name "Net-(C10-P2)") (class "Default")
      (node (ref "C10") (pin "2") (pinfunction "P2_2") (pintype "passive"))
      (node (ref "DA3") (pin "7") (pinfunction "ADJ_7") (pintype "passive"))
      (node (ref "R3") (pin "1") (pinfunction "1_1") (pintype "passive"))
      (node (ref "R4") (pin "1") (pinfunction "1_1") (pintype "passive"))
    )
    (net (code "37") (name "Net-(C13-P2)") (class "Default")
      (node (ref "C13") (pin "2") (pinfunction "P2_2") (pintype "passive"))
      (node (ref "DA2") (pin "4") (pinfunction "FB_4") (pintype "passive"))
      (node (ref "R2") (pin "1") (pinfunction "1_1") (pintype "passive"))
      (node (ref "R5") (pin "1") (pinfunction "1_1") (pintype "passive"))
    )
    (net (code "38") (name "Net-(C22-P1)") (class "Default")
      (node (ref "C22") (pin "1") (pinfunction "P1_1") (pintype "passive"))
      (node (ref "DD1") (pin "3") (pinfunction "PC14/OSC32_IN_3") (pintype "passive"))
      (node (ref "ZQ1") (pin "1") (pinfunction "1_1") (pintype "passive"))
    )
    (net (code "39") (name "Net-(C23-P1)") (class "Default")
      (node (ref "C23") (pin "1") (pinfunction "P1_1") (pintype "passive"))
      (node (ref "DD1") (pin "4") (pinfunction "PC15/OSC32_OUT_4") (pintype "passive"))
      (node (ref "ZQ1") (pin "2") (pinfunction "2_2") (pintype "passive"))
    )
    (net (code "40") (name "Net-(C28-Pad1)") (class "Default")
      (node (ref "C28") (pin "1") (pinfunction "1_1") (pintype "passive"))
      (node (ref "R14") (pin "1") (pinfunction "1_1") (pintype "passive"))
    )
    (net (code "41") (name "Net-(DA2-Boot)") (class "Default")
      (node (ref "C5") (pin "2") (pinfunction "2_2") (pintype "passive"))
      (node (ref "DA2") (pin "1") (pinfunction "Boot_1") (pintype "passive"))
    )
    (net (code "42") (name "Net-(DA2-SW)") (class "Default")
      (node (ref "C5") (pin "1") (pinfunction "1_1") (pintype "passive"))
      (node (ref "DA2") (pin "8") (pinfunction "SW_8") (pintype "passive"))
      (node (ref "L1") (pin "1") (pinfunction "1_1") (pintype "passive"))
      (node (ref "VD2") (pin "C") (pinfunction "2_C") (pintype "passive"))
    )
    (net (code "43") (name "Net-(DD1-PH0-OSC_IN)") (class "Default")
      (node (ref "DD1") (pin "5") (pinfunction "PH0-OSC_IN_5") (pintype "passive"))
      (node (ref "ZQ2") (pin "1") (pinfunction "1_1") (pintype "passive"))
    )
    (net (code "44") (name "Net-(DD1-PH1-OSC_OUT)") (class "Default")
      (node (ref "DD1") (pin "6") (pinfunction "PH1-OSC_OUT_6") (pintype "passive"))
      (node (ref "ZQ2") (pin "3") (pinfunction "3_3") (pintype "passive"))
    )
    (net (code "45") (name "Net-(VD3-anod)") (class "Default")
      (node (ref "R13") (pin "2") (pinfunction "2_2") (pintype "passive"))
      (node (ref "VD3") (pin "A") (pinfunction "anod_A") (pintype "passive"))
    )
    (net (code "46") (name "SIM_GND") (class "Default")
      (node (ref "D3") (pin "1") (pinfunction "Vss_1") (pintype "passive"))
      (node (ref "VT1") (pin "3") (pinfunction "D_3") (pintype "passive"))
      (node (ref "X1") (pin "5") (pinfunction "GND_5") (pintype "passive"))
    )
    (net (code "47") (name "SIM_VDD") (class "Default")
      (node (ref "C14") (pin "2") (pinfunction "P2_2") (pintype "passive"))
      (node (ref "D1") (pin "18") (pinfunction "SIM1_VDD_18") (pintype "power_in"))
      (node (ref "D3") (pin "8") (pinfunction "VDD_8") (pintype "passive"))
      (node (ref "R1") (pin "1") (pinfunction "1_1") (pintype "passive"))
      (node (ref "X1") (pin "1") (pinfunction "VCC_1") (pintype "passive"))
    )
    (net (code "48") (name "U_MAIN") (class "Default")
      (node (ref "C6") (pin "1") (pinfunction "1_1") (pintype "passive"))
      (node (ref "C7") (pin "1") (pinfunction "1_1") (pintype "passive"))
      (node (ref "DA2") (pin "5") (pinfunction "EN2_5") (pintype "passive"))
      (node (ref "DA2") (pin "7") (pinfunction "Vin_7") (pintype "passive"))
      (node (ref "R6") (pin "1") (pinfunction "1_1") (pintype "passive"))
      (node (ref "VD5") (pin "1") (pinfunction "DC+_1") (pintype "passive"))
    )
    (net (code "49") (name "unconnected-(D1A-1PPS-Pad60)") (class "Default")
      (node (ref "D1") (pin "60") (pinfunction "1PPS_60") (pintype "output"))
    )
    (net (code "50") (name "unconnected-(D1A-ADC-Pad38)") (class "Default")
      (node (ref "D1") (pin "38") (pinfunction "ADC_38") (pintype "input"))
    )
    (net (code "51") (name "unconnected-(D1A-BT_ANT-Pad20)") (class "Default")
      (node (ref "D1") (pin "20") (pinfunction "BT_ANT_20") (pintype "bidirectional"))
    )
    (net (code "52") (name "unconnected-(D1A-GPIO1-Pad57)") (class "Default")
      (node (ref "D1") (pin "57") (pinfunction "GPIO1_57") (pintype "bidirectional"))
    )
    (net (code "53") (name "unconnected-(D1A-GPIO2-Pad58)") (class "Default")
      (node (ref "D1") (pin "58") (pinfunction "GPIO2_58") (pintype "bidirectional"))
    )
    (net (code "54") (name "unconnected-(D1A-MCCA0-Pad49)") (class "Default")
      (node (ref "D1") (pin "49") (pinfunction "MCCA0_49") (pintype "bidirectional"))
    )
    (net (code "55") (name "unconnected-(D1A-MCCA1-Pad48)") (class "Default")
      (node (ref "D1") (pin "48") (pinfunction "MCCA1_48") (pintype "bidirectional"))
    )
    (net (code "56") (name "unconnected-(D1A-MCCA2-Pad47)") (class "Default")
      (node (ref "D1") (pin "47") (pinfunction "MCCA2_47") (pintype "bidirectional"))
    )
    (net (code "57") (name "unconnected-(D1A-MCCA3-Pad46)") (class "Default")
      (node (ref "D1") (pin "46") (pinfunction "MCCA3_46") (pintype "bidirectional"))
    )
    (net (code "58") (name "unconnected-(D1A-MCCK-Pad50)") (class "Default")
      (node (ref "D1") (pin "50") (pinfunction "MCCK_50") (pintype "bidirectional"))
    )
    (net (code "59") (name "unconnected-(D1A-MCCM0-Pad51)") (class "Default")
      (node (ref "D1") (pin "51") (pinfunction "MCCM0_51") (pintype "bidirectional"))
    )
    (net (code "60") (name "unconnected-(D1A-MICN-Pad10)") (class "Default")
      (node (ref "D1") (pin "10") (pinfunction "MICN_10") (pintype "input"))
    )
    (net (code "61") (name "unconnected-(D1A-MICP-Pad9)") (class "Default")
      (node (ref "D1") (pin "9") (pinfunction "MICP_9") (pintype "input"))
    )
    (net (code "62") (name "unconnected-(D1A-NETLIGHT-Pad41)") (class "Default")
      (node (ref "D1") (pin "41") (pinfunction "NETLIGHT_41") (pintype "output"))
    )
    (net (code "63") (name "unconnected-(D1A-RF_SYNC-Pad29)") (class "Default")
      (node (ref "D1") (pin "29") (pinfunction "RF_SYNC_29") (pintype "output"))
    )
    (net (code "64") (name "unconnected-(D1A-SCL-Pad65)") (class "Default")
      (node (ref "D1") (pin "65") (pinfunction "SCL_65") (pintype "output"))
    )
    (net (code "65") (name "unconnected-(D1A-SDA-Pad64)") (class "Default")
      (node (ref "D1") (pin "64") (pinfunction "SDA_64") (pintype "bidirectional"))
    )
    (net (code "66") (name "unconnected-(D1A-SIM1_DET-Pad14)") (class "Default")
      (node (ref "D1") (pin "14") (pinfunction "SIM1_DET_14") (pintype "input"))
    )
    (net (code "67") (name "unconnected-(D1A-SIM2_CLK-Pad54)") (class "Default")
      (node (ref "D1") (pin "54") (pinfunction "SIM2_CLK_54") (pintype "output"))
    )
    (net (code "68") (name "unconnected-(D1A-SIM2_DATA-Pad53)") (class "Default")
      (node (ref "D1") (pin "53") (pinfunction "SIM2_DATA_53") (pintype "bidirectional"))
    )
    (net (code "69") (name "unconnected-(D1A-SIM2_DET-Pad52)") (class "Default")
      (node (ref "D1") (pin "52") (pinfunction "SIM2_DET_52") (pintype "input"))
    )
    (net (code "70") (name "unconnected-(D1A-SIM2_RST-Pad55)") (class "Default")
      (node (ref "D1") (pin "55") (pinfunction "SIM2_RST_55") (pintype "output"))
    )
    (net (code "71") (name "unconnected-(D1A-SIM2_VDD-Pad56)") (class "Default")
      (node (ref "D1") (pin "56") (pinfunction "SIM2_VDD_56") (pintype "power_in"))
    )
    (net (code "72") (name "unconnected-(D1A-SPK1N-Pad12)") (class "Default")
      (node (ref "D1") (pin "12") (pinfunction "SPK1N_12") (pintype "output"))
    )
    (net (code "73") (name "unconnected-(D1A-SPK1P-Pad11)") (class "Default")
      (node (ref "D1") (pin "11") (pinfunction "SPK1P_11") (pintype "output"))
    )
    (net (code "74") (name "unconnected-(D1A-SPK2N-Pad43)") (class "Default")
      (node (ref "D1") (pin "43") (pinfunction "SPK2N_43") (pintype "output"))
    )
    (net (code "75") (name "unconnected-(D1A-SPK2P-Pad44)") (class "Default")
      (node (ref "D1") (pin "44") (pinfunction "SPK2P_44") (pintype "output"))
    )
    (net (code "76") (name "unconnected-(D1A-STATUS-Pad42)") (class "Default")
      (node (ref "D1") (pin "42") (pinfunction "STATUS_42") (pintype "output"))
    )
    (net (code "77") (name "unconnected-(D1A-UART1_CTS-Pad4)") (class "Default")
      (node (ref "D1") (pin "4") (pinfunction "UART1_CTS_4") (pintype "output"))
    )
    (net (code "78") (name "unconnected-(D1A-UART1_DCD-Pad5)") (class "Default")
      (node (ref "D1") (pin "5") (pinfunction "UART1_DCD_5") (pintype "output"))
    )
    (net (code "79") (name "unconnected-(D1A-UART1_DTR-Pad6)") (class "Default")
      (node (ref "D1") (pin "6") (pinfunction "UART1_DTR_6") (pintype "input"))
    )
    (net (code "80") (name "unconnected-(D1A-UART1_RI-Pad7)") (class "Default")
      (node (ref "D1") (pin "7") (pinfunction "UART1_RI_7") (pintype "output"))
    )
    (net (code "81") (name "unconnected-(D1A-UART1_RTS-Pad3)") (class "Default")
      (node (ref "D1") (pin "3") (pinfunction "UART1_RTS_3") (pintype "input"))
    )
    (net (code "82") (name "unconnected-(D1A-UART2_RXD-Pad23)") (class "Default")
      (node (ref "D1") (pin "23") (pinfunction "UART2_RXD_23") (pintype "input"))
    )
    (net (code "83") (name "unconnected-(D1A-UART2_TXD-Pad22)") (class "Default")
      (node (ref "D1") (pin "22") (pinfunction "UART2_TXD_22") (pintype "output"))
    )
    (net (code "84") (name "unconnected-(D1A-USB_DM-Pad26)") (class "Default")
      (node (ref "D1") (pin "26") (pinfunction "USB_DM_26") (pintype "bidirectional"))
    )
    (net (code "85") (name "unconnected-(D1A-USB_DP-Pad25)") (class "Default")
      (node (ref "D1") (pin "25") (pinfunction "USB_DP_25") (pintype "bidirectional"))
    )
    (net (code "86") (name "unconnected-(D1A-USB_VBUS-Pad24)") (class "Default")
      (node (ref "D1") (pin "24") (pinfunction "USB_VBUS_24") (pintype "power_in"))
    )
    (net (code "87") (name "unconnected-(D1B-GND-Pad8)") (class "Default")
      (node (ref "D1") (pin "8") (pinfunction "GND_8") (pintype "power_in"))
    )
    (net (code "88") (name "unconnected-(D1B-VDD_EXT-Pad40)") (class "Default")
      (node (ref "D1") (pin "40") (pinfunction "VDD_EXT_40") (pintype "power_in"))
    )
    (net (code "89") (name "unconnected-(D3-NA-Pad2)") (class "Default")
      (node (ref "D3") (pin "2") (pinfunction "NA_2") (pintype "passive"))
    )
    (net (code "90") (name "unconnected-(DA1-NC{slash}FB-Pad4)") (class "Default")
      (node (ref "DA1") (pin "4") (pinfunction "NC/FB_4") (pintype "passive"))
    )
    (net (code "91") (name "unconnected-(DA2-PGOOD-Pad2)") (class "Default")
      (node (ref "DA2") (pin "2") (pinfunction "PGOOD_2") (pintype "passive"))
    )
    (net (code "92") (name "unconnected-(DA3-PGOOD-Pad1)") (class "Default")
      (node (ref "DA3") (pin "1") (pinfunction "PGOOD_1") (pintype "output+no_connect"))
    )
    (net (code "93") (name "unconnected-(DD1-PA1-Pad11)") (class "Default")
      (node (ref "DD1") (pin "11") (pinfunction "PA1_11") (pintype "passive"))
    )
    (net (code "94") (name "unconnected-(DD1-PA8-Pad29)") (class "Default")
      (node (ref "DD1") (pin "29") (pinfunction "PA8_29") (pintype "passive"))
    )
    (net (code "95") (name "unconnected-(DD1-PA12-Pad33)") (class "Default")
      (node (ref "DD1") (pin "33") (pinfunction "PA12_33") (pintype "passive"))
    )
    (net (code "96") (name "unconnected-(DD1-PB3{slash}JTDO-Pad39)") (class "Default")
      (node (ref "DD1") (pin "39") (pinfunction "PB3/JTDO_39") (pintype "passive"))
    )
    (net (code "97") (name "unconnected-(DD1-PB4{slash}nJTRST-Pad40)") (class "Default")
      (node (ref "DD1") (pin "40") (pinfunction "PB4/nJTRST_40") (pintype "passive"))
    )
    (net (code "98") (name "unconnected-(DD1-PB5-Pad41)") (class "Default")
      (node (ref "DD1") (pin "41") (pinfunction "PB5_41") (pintype "passive"))
    )
    (net (code "99") (name "unconnected-(DD1-PB6-Pad42)") (class "Default")
      (node (ref "DD1") (pin "42") (pinfunction "PB6_42") (pintype "passive"))
    )
    (net (code "100") (name "unconnected-(DD1-PB7-Pad43)") (class "Default")
      (node (ref "DD1") (pin "43") (pinfunction "PB7_43") (pintype "passive"))
    )
    (net (code "101") (name "unconnected-(DD1-PB8-Pad45)") (class "Default")
      (node (ref "DD1") (pin "45") (pinfunction "PB8_45") (pintype "passive"))
    )
    (net (code "102") (name "unconnected-(DD1-PB13{slash}SCK2-Pad26)") (class "Default")
      (node (ref "DD1") (pin "26") (pinfunction "PB13/SCK2_26") (pintype "passive"))
    )
    (net (code "103") (name "unconnected-(DD1-PB14{slash}MISO2-Pad27)") (class "Default")
      (node (ref "DD1") (pin "27") (pinfunction "PB14/MISO2_27") (pintype "passive"))
    )
    (net (code "104") (name "unconnected-(DD1-PC13-WKUP2-Pad2)") (class "Default")
      (node (ref "DD1") (pin "2") (pinfunction "PC13-WKUP2_2") (pintype "passive"))
    )
    (net (code "105") (name "unconnected-(DD1-TPAD-Pad49)") (class "Default")
      (node (ref "DD1") (pin "49") (pinfunction "TPAD_49") (pintype "passive"))
    )
    (net (code "106") (name "unconnected-(DD2-INT2-Pad9)") (class "Default")
      (node (ref "DD2") (pin "9") (pinfunction "INT2_9") (pintype "passive"))
    )
    (net (code "107") (name "unconnected-(DD2-NC-Pad2)") (class "Default")
      (node (ref "DD2") (pin "2") (pinfunction "NC_2") (pintype "passive"))
    )
    (net (code "108") (name "unconnected-(DD2-NC-Pad3)") (class "Default")
      (node (ref "DD2") (pin "3") (pinfunction "NC_3") (pintype "passive"))
    )
    (net (code "109") (name "unconnected-(X1-VPP-Pad6)") (class "Default")
      (node (ref "X1") (pin "6") (pinfunction "VPP_6") (pintype "passive"))
    )
  )
)
